# choobMatrix.net
KiCad netlist of a schematic drawn in EAGLE
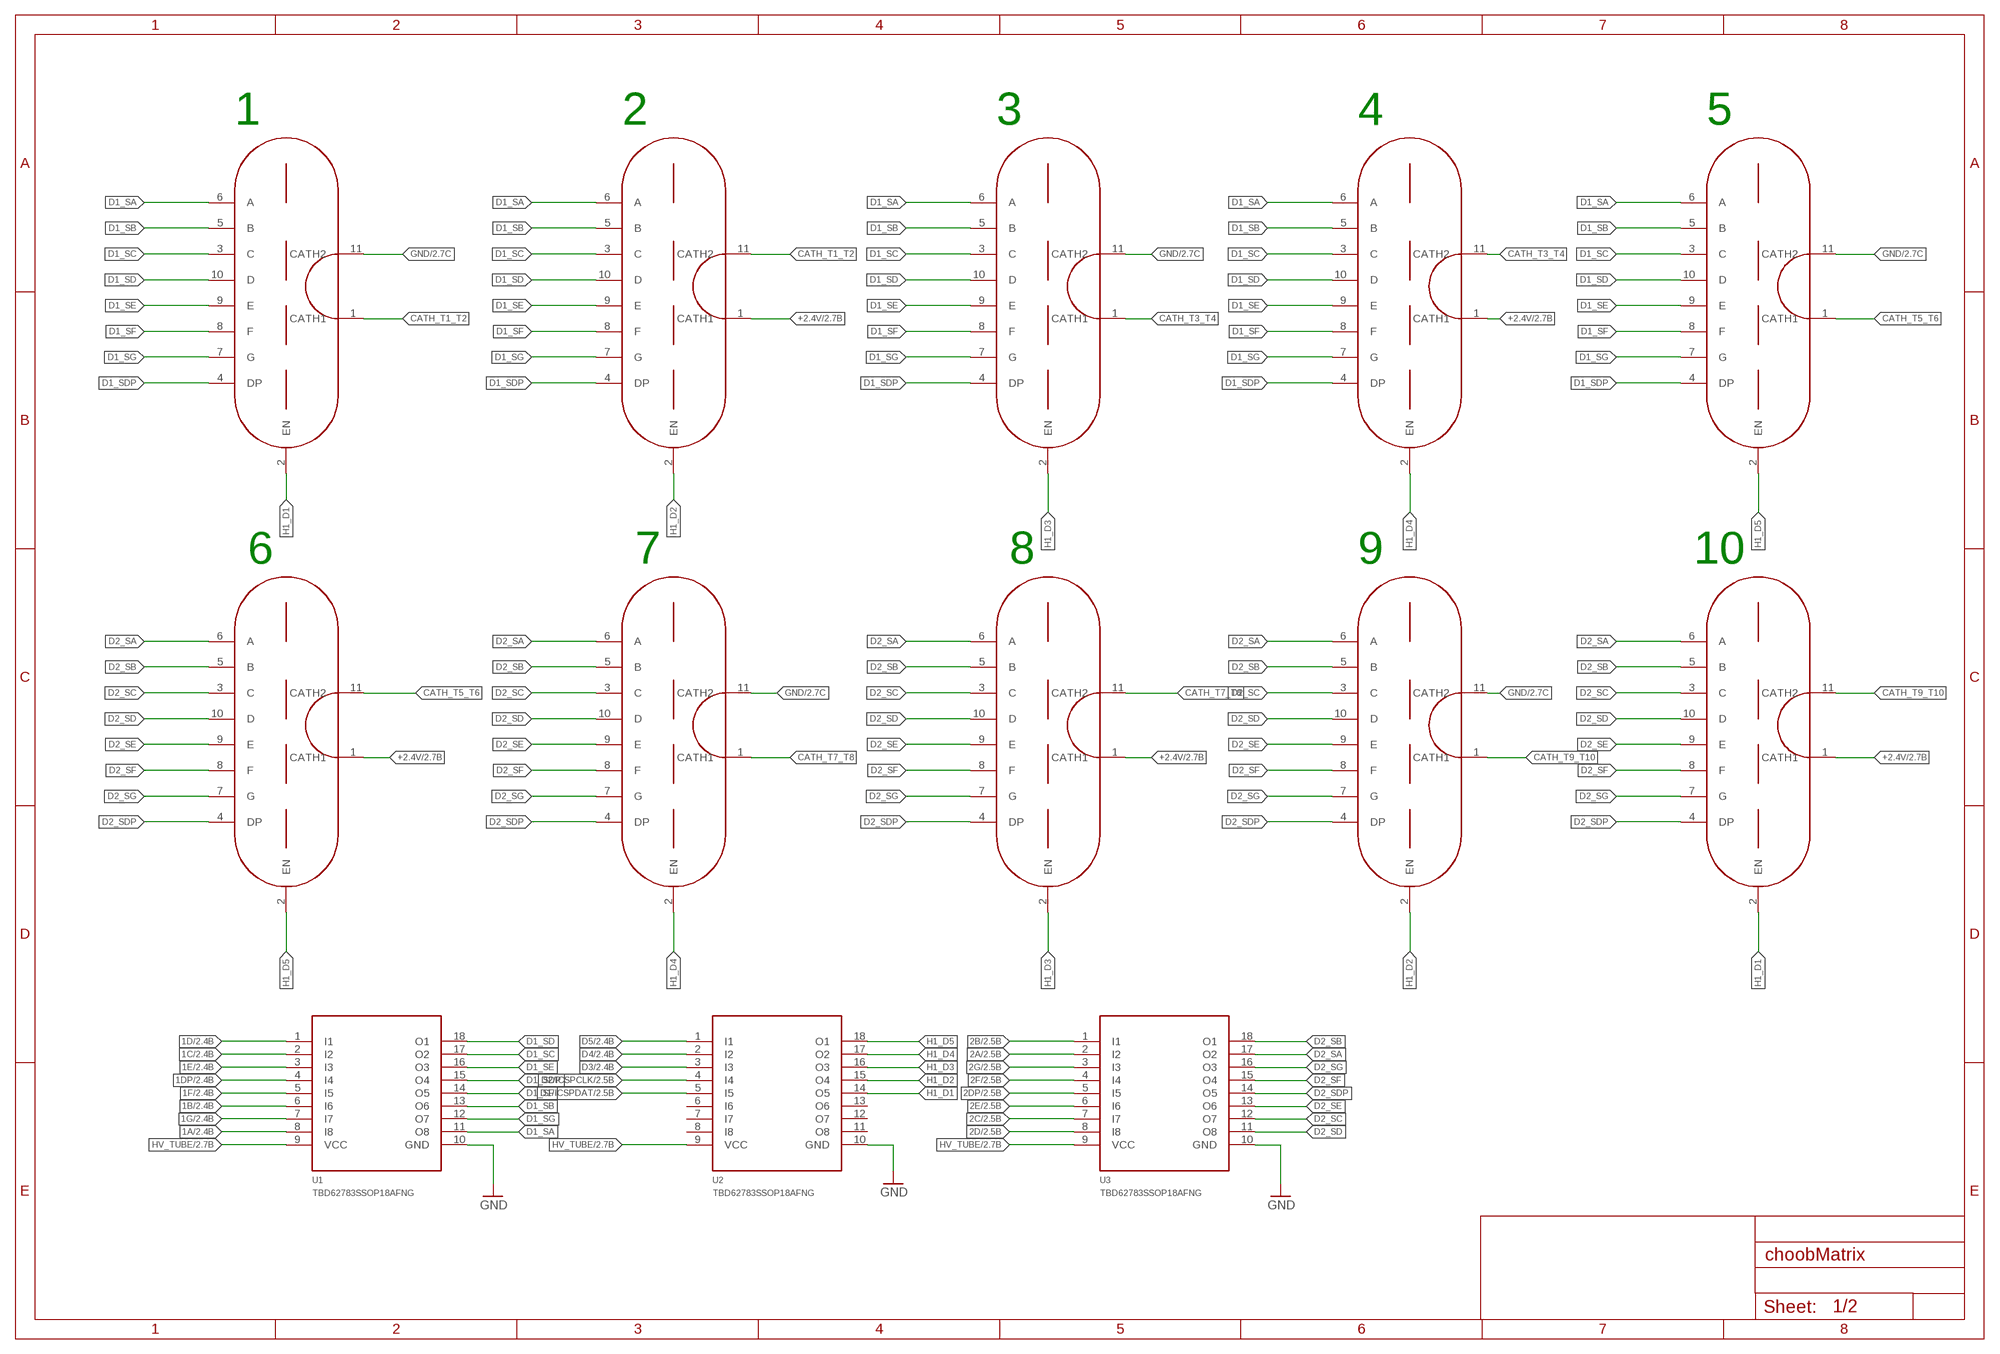
[diagram p0: schematic, sheet 1]
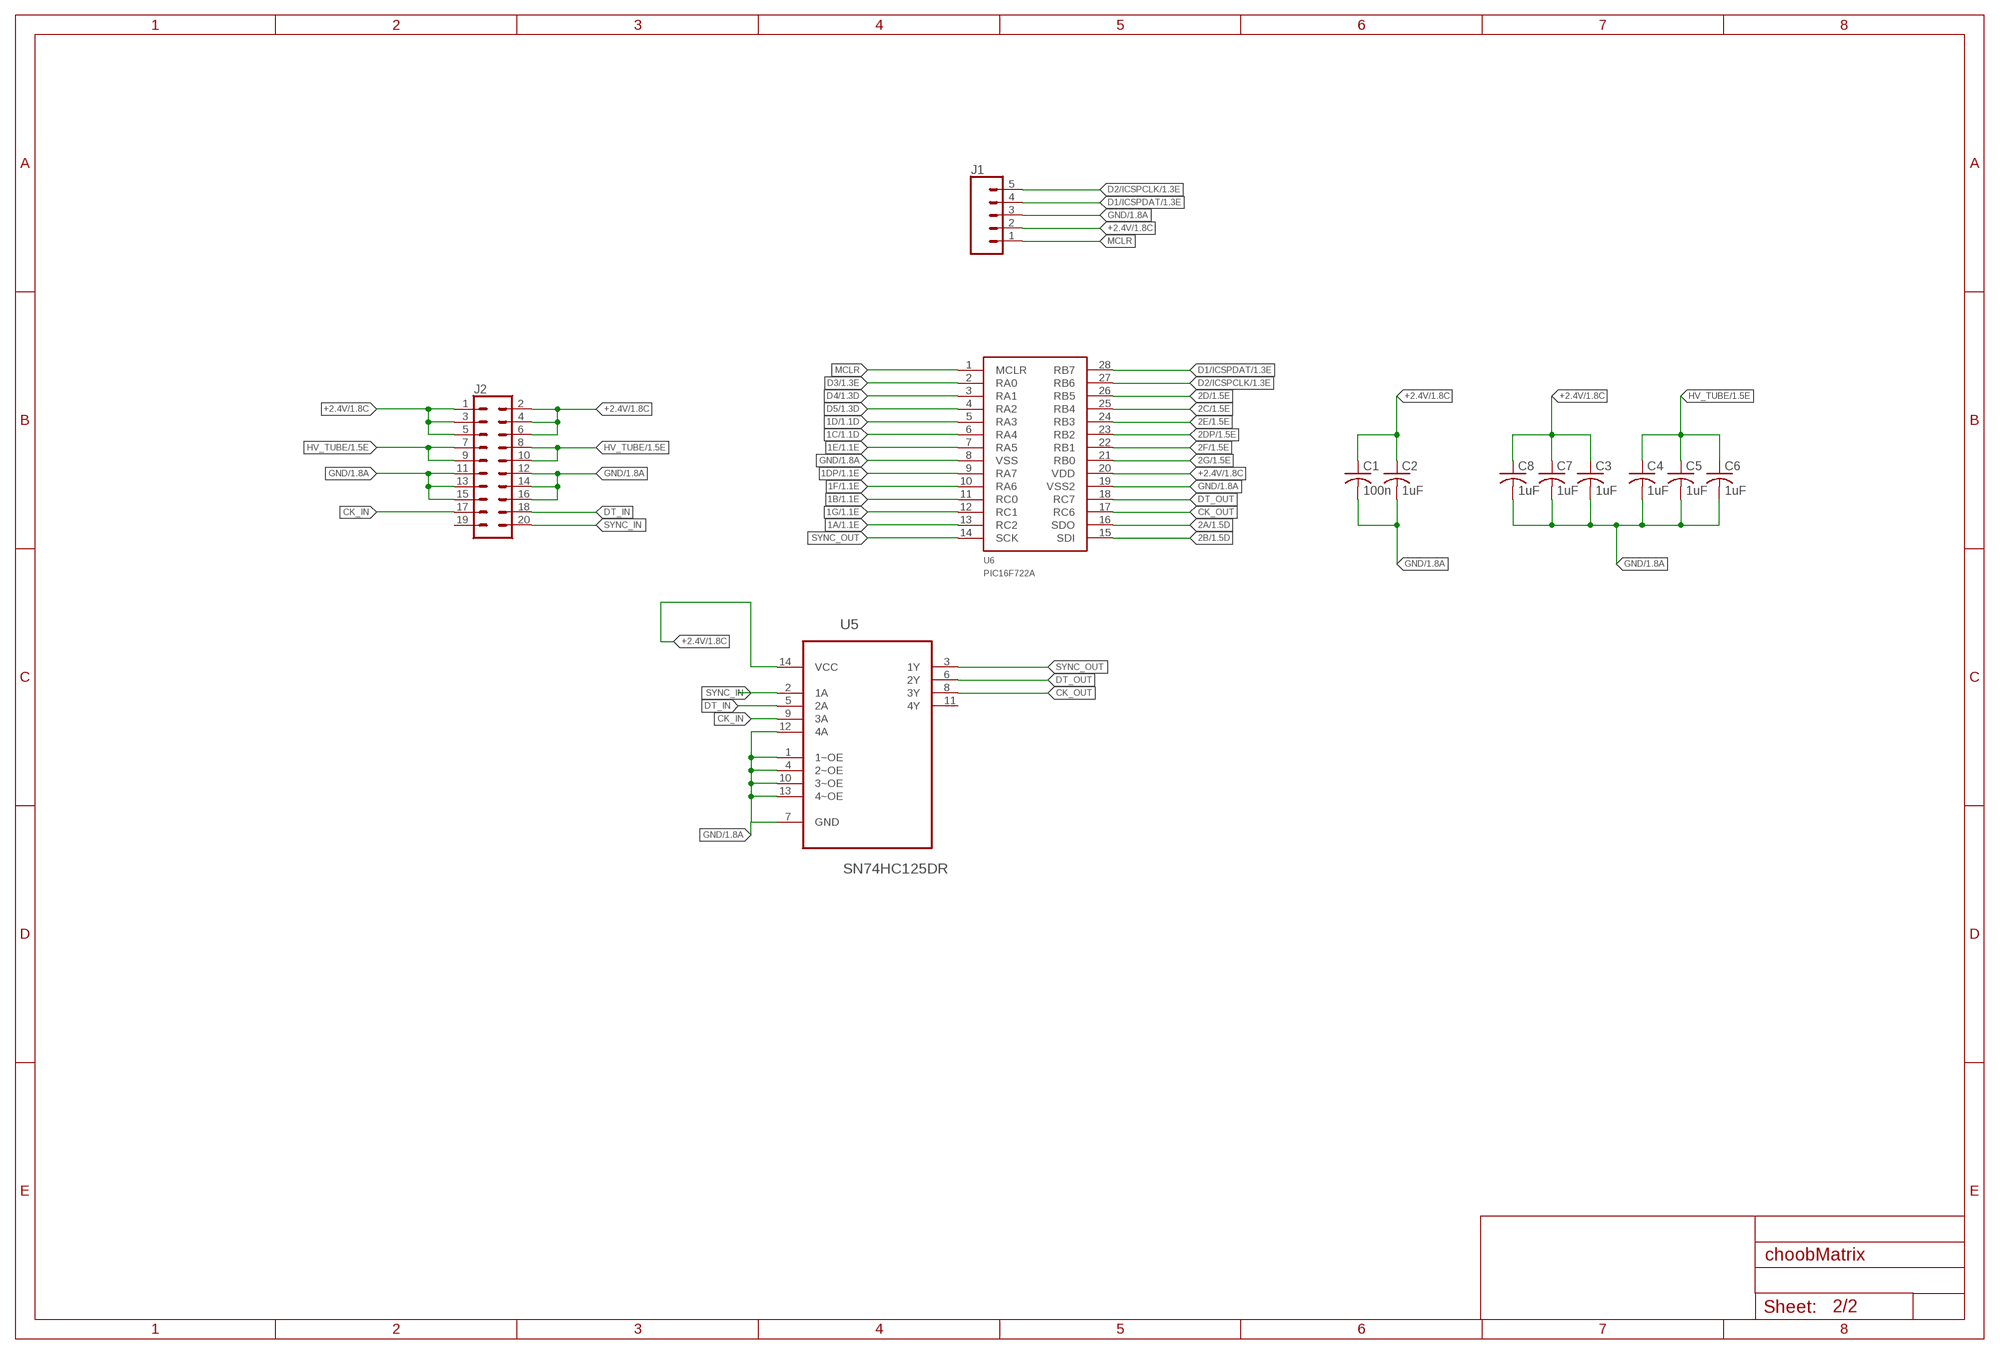
[diagram p1: schematic, sheet 2]

(export (version "E")
  (design (tool "Eeschema 10.0.6"))
  (components
    (comp (ref "C1")
      (value "100n")
      (footprint "eagle-import:C0805K")
      (libsource (lib "eagle-import") (part "C-USC0805K"))
    )
    (comp (ref "C2")
      (value "1uF")
      (footprint "eagle-import:C0805K")
      (libsource (lib "eagle-import") (part "C-USC0805K"))
    )
    (comp (ref "C3")
      (value "1uF")
      (footprint "eagle-import:C0805K")
      (libsource (lib "eagle-import") (part "C-USC0805K"))
    )
    (comp (ref "C4")
      (value "1uF")
      (footprint "eagle-import:C0805K")
      (libsource (lib "eagle-import") (part "C-USC0805K"))
    )
    (comp (ref "C5")
      (value "1uF")
      (footprint "eagle-import:C0805K")
      (libsource (lib "eagle-import") (part "C-USC0805K"))
    )
    (comp (ref "C6")
      (value "1uF")
      (footprint "eagle-import:C0805K")
      (libsource (lib "eagle-import") (part "C-USC0805K"))
    )
    (comp (ref "C7")
      (value "1uF")
      (footprint "eagle-import:C0805K")
      (libsource (lib "eagle-import") (part "C-USC0805K"))
    )
    (comp (ref "C8")
      (value "1uF")
      (footprint "eagle-import:C0805K")
      (libsource (lib "eagle-import") (part "C-USC0805K"))
    )
    (comp (ref "J1")
      (value "CONN_05")
      (footprint "eagle-import:1X05")
      (libsource (lib "eagle-import") (part "CONN_05"))
    )
    (comp (ref "J2")
      (value "CONN_10X2NOSILK")
      (footprint "eagle-import:2X10_NOSILK")
      (libsource (lib "eagle-import") (part "CONN_10X2NOSILK"))
    )
    (comp (ref "U5")
      (value "SN74HC125DR")
      (footprint "eagle-import:SOIC127P600X175-14N")
      (fields (field (name "MF") "Texas Instruments"))
      (libsource (lib "eagle-import") (part "SN74HC125DR"))
    )
    (comp (ref "U6")
      (value "PIC16F722A")
      (footprint "eagle-import:SOP65P780X200-28N")
      (libsource (lib "eagle-import") (part "PIC16F722A"))
    )
    (comp (ref "T1")
      (value "IV11")
      (footprint "eagle-import:IV11")
      (libsource (lib "eagle-import") (part "IV11"))
    )
    (comp (ref "T2")
      (value "IV11")
      (footprint "eagle-import:IV11")
      (libsource (lib "eagle-import") (part "IV11"))
    )
    (comp (ref "T3")
      (value "IV11")
      (footprint "eagle-import:IV11")
      (libsource (lib "eagle-import") (part "IV11"))
    )
    (comp (ref "T4")
      (value "IV11")
      (footprint "eagle-import:IV11")
      (libsource (lib "eagle-import") (part "IV11"))
    )
    (comp (ref "T5")
      (value "IV11")
      (footprint "eagle-import:IV11")
      (libsource (lib "eagle-import") (part "IV11"))
    )
    (comp (ref "T6")
      (value "IV11")
      (footprint "eagle-import:IV11")
      (libsource (lib "eagle-import") (part "IV11"))
    )
    (comp (ref "T7")
      (value "IV11")
      (footprint "eagle-import:IV11")
      (libsource (lib "eagle-import") (part "IV11"))
    )
    (comp (ref "T8")
      (value "IV11")
      (footprint "eagle-import:IV11")
      (libsource (lib "eagle-import") (part "IV11"))
    )
    (comp (ref "T9")
      (value "IV11")
      (footprint "eagle-import:IV11")
      (libsource (lib "eagle-import") (part "IV11"))
    )
    (comp (ref "T10")
      (value "IV11")
      (footprint "eagle-import:IV11")
      (libsource (lib "eagle-import") (part "IV11"))
    )
    (comp (ref "U1")
      (value "TBD62783SSOP18AFNG")
      (footprint "eagle-import:SOP65P640X15-18")
      (libsource (lib "eagle-import") (part "TBD62783SSOP18AFNG"))
    )
    (comp (ref "U2")
      (value "TBD62783SSOP18AFNG")
      (footprint "eagle-import:SOP65P640X15-18")
      (libsource (lib "eagle-import") (part "TBD62783SSOP18AFNG"))
    )
    (comp (ref "U3")
      (value "TBD62783SSOP18AFNG")
      (footprint "eagle-import:SOP65P640X15-18")
      (libsource (lib "eagle-import") (part "TBD62783SSOP18AFNG"))
    )
  )
  (nets
    (net (code "1") (name "+2.4V") (class "Default")
      (node (ref "C1") (pin "1") (pinfunction "1_1") (pintype "passive"))
      (node (ref "C2") (pin "1") (pinfunction "1_1") (pintype "passive"))
      (node (ref "C3") (pin "1") (pinfunction "1_1") (pintype "passive"))
      (node (ref "C7") (pin "1") (pinfunction "1_1") (pintype "passive"))
      (node (ref "C8") (pin "1") (pinfunction "1_1") (pintype "passive"))
      (node (ref "J1") (pin "2") (pinfunction "2_2") (pintype "passive"))
      (node (ref "J2") (pin "1") (pinfunction "1_1") (pintype "passive"))
      (node (ref "J2") (pin "2") (pinfunction "2_2") (pintype "passive"))
      (node (ref "J2") (pin "3") (pinfunction "3_3") (pintype "passive"))
      (node (ref "J2") (pin "4") (pinfunction "4_4") (pintype "passive"))
      (node (ref "J2") (pin "5") (pinfunction "5_5") (pintype "passive"))
      (node (ref "J2") (pin "6") (pinfunction "6_6") (pintype "passive"))
      (node (ref "T10") (pin "1") (pinfunction "CATH1_1") (pintype "bidirectional"))
      (node (ref "T2") (pin "1") (pinfunction "CATH1_1") (pintype "bidirectional"))
      (node (ref "T4") (pin "1") (pinfunction "CATH1_1") (pintype "bidirectional"))
      (node (ref "T6") (pin "1") (pinfunction "CATH1_1") (pintype "bidirectional"))
      (node (ref "T8") (pin "1") (pinfunction "CATH1_1") (pintype "bidirectional"))
      (node (ref "U5") (pin "14") (pinfunction "VCC_14") (pintype "power_in"))
      (node (ref "U6") (pin "20") (pinfunction "VDD_20") (pintype "bidirectional"))
    )
    (net (code "2") (name "1A") (class "Default")
      (node (ref "U1") (pin "8") (pinfunction "I8_8") (pintype "bidirectional"))
      (node (ref "U6") (pin "13") (pinfunction "RC2_13") (pintype "bidirectional"))
    )
    (net (code "3") (name "1B") (class "Default")
      (node (ref "U1") (pin "6") (pinfunction "I6_6") (pintype "bidirectional"))
      (node (ref "U6") (pin "11") (pinfunction "RC0_11") (pintype "bidirectional"))
    )
    (net (code "4") (name "1C") (class "Default")
      (node (ref "U1") (pin "2") (pinfunction "I2_2") (pintype "bidirectional"))
      (node (ref "U6") (pin "6") (pinfunction "RA4_6") (pintype "bidirectional"))
    )
    (net (code "5") (name "1D") (class "Default")
      (node (ref "U1") (pin "1") (pinfunction "I1_1") (pintype "bidirectional"))
      (node (ref "U6") (pin "5") (pinfunction "RA3_5") (pintype "bidirectional"))
    )
    (net (code "6") (name "1DP") (class "Default")
      (node (ref "U1") (pin "4") (pinfunction "I4_4") (pintype "bidirectional"))
      (node (ref "U6") (pin "9") (pinfunction "RA7_9") (pintype "bidirectional"))
    )
    (net (code "7") (name "1E") (class "Default")
      (node (ref "U1") (pin "3") (pinfunction "I3_3") (pintype "bidirectional"))
      (node (ref "U6") (pin "7") (pinfunction "RA5_7") (pintype "bidirectional"))
    )
    (net (code "8") (name "1F") (class "Default")
      (node (ref "U1") (pin "5") (pinfunction "I5_5") (pintype "bidirectional"))
      (node (ref "U6") (pin "10") (pinfunction "RA6_10") (pintype "bidirectional"))
    )
    (net (code "9") (name "1G") (class "Default")
      (node (ref "U1") (pin "7") (pinfunction "I7_7") (pintype "bidirectional"))
      (node (ref "U6") (pin "12") (pinfunction "RC1_12") (pintype "bidirectional"))
    )
    (net (code "10") (name "2A") (class "Default")
      (node (ref "U3") (pin "2") (pinfunction "I2_2") (pintype "bidirectional"))
      (node (ref "U6") (pin "16") (pinfunction "SDO_16") (pintype "bidirectional"))
    )
    (net (code "11") (name "2B") (class "Default")
      (node (ref "U3") (pin "1") (pinfunction "I1_1") (pintype "bidirectional"))
      (node (ref "U6") (pin "15") (pinfunction "SDI_15") (pintype "bidirectional"))
    )
    (net (code "12") (name "2C") (class "Default")
      (node (ref "U3") (pin "7") (pinfunction "I7_7") (pintype "bidirectional"))
      (node (ref "U6") (pin "25") (pinfunction "RB4_25") (pintype "bidirectional"))
    )
    (net (code "13") (name "2D") (class "Default")
      (node (ref "U3") (pin "8") (pinfunction "I8_8") (pintype "bidirectional"))
      (node (ref "U6") (pin "26") (pinfunction "RB5_26") (pintype "bidirectional"))
    )
    (net (code "14") (name "2DP") (class "Default")
      (node (ref "U3") (pin "5") (pinfunction "I5_5") (pintype "bidirectional"))
      (node (ref "U6") (pin "23") (pinfunction "RB2_23") (pintype "bidirectional"))
    )
    (net (code "15") (name "2E") (class "Default")
      (node (ref "U3") (pin "6") (pinfunction "I6_6") (pintype "bidirectional"))
      (node (ref "U6") (pin "24") (pinfunction "RB3_24") (pintype "bidirectional"))
    )
    (net (code "16") (name "2F") (class "Default")
      (node (ref "U3") (pin "4") (pinfunction "I4_4") (pintype "bidirectional"))
      (node (ref "U6") (pin "22") (pinfunction "RB1_22") (pintype "bidirectional"))
    )
    (net (code "17") (name "2G") (class "Default")
      (node (ref "U3") (pin "3") (pinfunction "I3_3") (pintype "bidirectional"))
      (node (ref "U6") (pin "21") (pinfunction "RB0_21") (pintype "bidirectional"))
    )
    (net (code "18") (name "CATH_T1_T2") (class "Default")
      (node (ref "T1") (pin "1") (pinfunction "CATH1_1") (pintype "bidirectional"))
      (node (ref "T2") (pin "11") (pinfunction "CATH2_11") (pintype "bidirectional"))
    )
    (net (code "19") (name "CATH_T3_T4") (class "Default")
      (node (ref "T3") (pin "1") (pinfunction "CATH1_1") (pintype "bidirectional"))
      (node (ref "T4") (pin "11") (pinfunction "CATH2_11") (pintype "bidirectional"))
    )
    (net (code "20") (name "CATH_T5_T6") (class "Default")
      (node (ref "T5") (pin "1") (pinfunction "CATH1_1") (pintype "bidirectional"))
      (node (ref "T6") (pin "11") (pinfunction "CATH2_11") (pintype "bidirectional"))
    )
    (net (code "21") (name "CATH_T7_T8") (class "Default")
      (node (ref "T7") (pin "1") (pinfunction "CATH1_1") (pintype "bidirectional"))
      (node (ref "T8") (pin "11") (pinfunction "CATH2_11") (pintype "bidirectional"))
    )
    (net (code "22") (name "CATH_T9_T10") (class "Default")
      (node (ref "T10") (pin "11") (pinfunction "CATH2_11") (pintype "bidirectional"))
      (node (ref "T9") (pin "1") (pinfunction "CATH1_1") (pintype "bidirectional"))
    )
    (net (code "23") (name "CK_IN") (class "Default")
      (node (ref "J2") (pin "17") (pinfunction "17_17") (pintype "passive"))
      (node (ref "U5") (pin "9") (pinfunction "3A_9") (pintype "input"))
    )
    (net (code "24") (name "CK_OUT") (class "Default")
      (node (ref "U5") (pin "8") (pinfunction "3Y_8") (pintype "output"))
      (node (ref "U6") (pin "17") (pinfunction "RC6_17") (pintype "bidirectional"))
    )
    (net (code "25") (name "D1_SA") (class "Default")
      (node (ref "T1") (pin "6") (pinfunction "A_6") (pintype "bidirectional"))
      (node (ref "T2") (pin "6") (pinfunction "A_6") (pintype "bidirectional"))
      (node (ref "T3") (pin "6") (pinfunction "A_6") (pintype "bidirectional"))
      (node (ref "T4") (pin "6") (pinfunction "A_6") (pintype "bidirectional"))
      (node (ref "T5") (pin "6") (pinfunction "A_6") (pintype "bidirectional"))
      (node (ref "U1") (pin "11") (pinfunction "O8_11") (pintype "bidirectional"))
    )
    (net (code "26") (name "D1_SB") (class "Default")
      (node (ref "T1") (pin "5") (pinfunction "B_5") (pintype "bidirectional"))
      (node (ref "T2") (pin "5") (pinfunction "B_5") (pintype "bidirectional"))
      (node (ref "T3") (pin "5") (pinfunction "B_5") (pintype "bidirectional"))
      (node (ref "T4") (pin "5") (pinfunction "B_5") (pintype "bidirectional"))
      (node (ref "T5") (pin "5") (pinfunction "B_5") (pintype "bidirectional"))
      (node (ref "U1") (pin "13") (pinfunction "O6_13") (pintype "bidirectional"))
    )
    (net (code "27") (name "D1_SC") (class "Default")
      (node (ref "T1") (pin "3") (pinfunction "C_3") (pintype "bidirectional"))
      (node (ref "T2") (pin "3") (pinfunction "C_3") (pintype "bidirectional"))
      (node (ref "T3") (pin "3") (pinfunction "C_3") (pintype "bidirectional"))
      (node (ref "T4") (pin "3") (pinfunction "C_3") (pintype "bidirectional"))
      (node (ref "T5") (pin "3") (pinfunction "C_3") (pintype "bidirectional"))
      (node (ref "U1") (pin "17") (pinfunction "O2_17") (pintype "bidirectional"))
    )
    (net (code "28") (name "D1_SD") (class "Default")
      (node (ref "T1") (pin "10") (pinfunction "D_10") (pintype "bidirectional"))
      (node (ref "T2") (pin "10") (pinfunction "D_10") (pintype "bidirectional"))
      (node (ref "T3") (pin "10") (pinfunction "D_10") (pintype "bidirectional"))
      (node (ref "T4") (pin "10") (pinfunction "D_10") (pintype "bidirectional"))
      (node (ref "T5") (pin "10") (pinfunction "D_10") (pintype "bidirectional"))
      (node (ref "U1") (pin "18") (pinfunction "O1_18") (pintype "bidirectional"))
    )
    (net (code "29") (name "D1_SDP") (class "Default")
      (node (ref "T1") (pin "4") (pinfunction "DP_4") (pintype "bidirectional"))
      (node (ref "T2") (pin "4") (pinfunction "DP_4") (pintype "bidirectional"))
      (node (ref "T3") (pin "4") (pinfunction "DP_4") (pintype "bidirectional"))
      (node (ref "T4") (pin "4") (pinfunction "DP_4") (pintype "bidirectional"))
      (node (ref "T5") (pin "4") (pinfunction "DP_4") (pintype "bidirectional"))
      (node (ref "U1") (pin "15") (pinfunction "O4_15") (pintype "bidirectional"))
    )
    (net (code "30") (name "D1_SE") (class "Default")
      (node (ref "T1") (pin "9") (pinfunction "E_9") (pintype "bidirectional"))
      (node (ref "T2") (pin "9") (pinfunction "E_9") (pintype "bidirectional"))
      (node (ref "T3") (pin "9") (pinfunction "E_9") (pintype "bidirectional"))
      (node (ref "T4") (pin "9") (pinfunction "E_9") (pintype "bidirectional"))
      (node (ref "T5") (pin "9") (pinfunction "E_9") (pintype "bidirectional"))
      (node (ref "U1") (pin "16") (pinfunction "O3_16") (pintype "bidirectional"))
    )
    (net (code "31") (name "D1_SF") (class "Default")
      (node (ref "T1") (pin "8") (pinfunction "F_8") (pintype "bidirectional"))
      (node (ref "T2") (pin "8") (pinfunction "F_8") (pintype "bidirectional"))
      (node (ref "T3") (pin "8") (pinfunction "F_8") (pintype "bidirectional"))
      (node (ref "T4") (pin "8") (pinfunction "F_8") (pintype "bidirectional"))
      (node (ref "T5") (pin "8") (pinfunction "F_8") (pintype "bidirectional"))
      (node (ref "U1") (pin "14") (pinfunction "O5_14") (pintype "bidirectional"))
    )
    (net (code "32") (name "D1_SG") (class "Default")
      (node (ref "T1") (pin "7") (pinfunction "G_7") (pintype "bidirectional"))
      (node (ref "T2") (pin "7") (pinfunction "G_7") (pintype "bidirectional"))
      (node (ref "T3") (pin "7") (pinfunction "G_7") (pintype "bidirectional"))
      (node (ref "T4") (pin "7") (pinfunction "G_7") (pintype "bidirectional"))
      (node (ref "T5") (pin "7") (pinfunction "G_7") (pintype "bidirectional"))
      (node (ref "U1") (pin "12") (pinfunction "O7_12") (pintype "bidirectional"))
    )
    (net (code "33") (name "D1{slash}ICSPDAT") (class "Default")
      (node (ref "J1") (pin "4") (pinfunction "4_4") (pintype "passive"))
      (node (ref "U2") (pin "5") (pinfunction "I5_5") (pintype "bidirectional"))
      (node (ref "U6") (pin "28") (pinfunction "RB7_28") (pintype "bidirectional"))
    )
    (net (code "34") (name "D2_SA") (class "Default")
      (node (ref "T10") (pin "6") (pinfunction "A_6") (pintype "bidirectional"))
      (node (ref "T6") (pin "6") (pinfunction "A_6") (pintype "bidirectional"))
      (node (ref "T7") (pin "6") (pinfunction "A_6") (pintype "bidirectional"))
      (node (ref "T8") (pin "6") (pinfunction "A_6") (pintype "bidirectional"))
      (node (ref "T9") (pin "6") (pinfunction "A_6") (pintype "bidirectional"))
      (node (ref "U3") (pin "17") (pinfunction "O2_17") (pintype "bidirectional"))
    )
    (net (code "35") (name "D2_SB") (class "Default")
      (node (ref "T10") (pin "5") (pinfunction "B_5") (pintype "bidirectional"))
      (node (ref "T6") (pin "5") (pinfunction "B_5") (pintype "bidirectional"))
      (node (ref "T7") (pin "5") (pinfunction "B_5") (pintype "bidirectional"))
      (node (ref "T8") (pin "5") (pinfunction "B_5") (pintype "bidirectional"))
      (node (ref "T9") (pin "5") (pinfunction "B_5") (pintype "bidirectional"))
      (node (ref "U3") (pin "18") (pinfunction "O1_18") (pintype "bidirectional"))
    )
    (net (code "36") (name "D2_SC") (class "Default")
      (node (ref "T10") (pin "3") (pinfunction "C_3") (pintype "bidirectional"))
      (node (ref "T6") (pin "3") (pinfunction "C_3") (pintype "bidirectional"))
      (node (ref "T7") (pin "3") (pinfunction "C_3") (pintype "bidirectional"))
      (node (ref "T8") (pin "3") (pinfunction "C_3") (pintype "bidirectional"))
      (node (ref "T9") (pin "3") (pinfunction "C_3") (pintype "bidirectional"))
      (node (ref "U3") (pin "12") (pinfunction "O7_12") (pintype "bidirectional"))
    )
    (net (code "37") (name "D2_SD") (class "Default")
      (node (ref "T10") (pin "10") (pinfunction "D_10") (pintype "bidirectional"))
      (node (ref "T6") (pin "10") (pinfunction "D_10") (pintype "bidirectional"))
      (node (ref "T7") (pin "10") (pinfunction "D_10") (pintype "bidirectional"))
      (node (ref "T8") (pin "10") (pinfunction "D_10") (pintype "bidirectional"))
      (node (ref "T9") (pin "10") (pinfunction "D_10") (pintype "bidirectional"))
      (node (ref "U3") (pin "11") (pinfunction "O8_11") (pintype "bidirectional"))
    )
    (net (code "38") (name "D2_SDP") (class "Default")
      (node (ref "T10") (pin "4") (pinfunction "DP_4") (pintype "bidirectional"))
      (node (ref "T6") (pin "4") (pinfunction "DP_4") (pintype "bidirectional"))
      (node (ref "T7") (pin "4") (pinfunction "DP_4") (pintype "bidirectional"))
      (node (ref "T8") (pin "4") (pinfunction "DP_4") (pintype "bidirectional"))
      (node (ref "T9") (pin "4") (pinfunction "DP_4") (pintype "bidirectional"))
      (node (ref "U3") (pin "14") (pinfunction "O5_14") (pintype "bidirectional"))
    )
    (net (code "39") (name "D2_SE") (class "Default")
      (node (ref "T10") (pin "9") (pinfunction "E_9") (pintype "bidirectional"))
      (node (ref "T6") (pin "9") (pinfunction "E_9") (pintype "bidirectional"))
      (node (ref "T7") (pin "9") (pinfunction "E_9") (pintype "bidirectional"))
      (node (ref "T8") (pin "9") (pinfunction "E_9") (pintype "bidirectional"))
      (node (ref "T9") (pin "9") (pinfunction "E_9") (pintype "bidirectional"))
      (node (ref "U3") (pin "13") (pinfunction "O6_13") (pintype "bidirectional"))
    )
    (net (code "40") (name "D2_SF") (class "Default")
      (node (ref "T10") (pin "8") (pinfunction "F_8") (pintype "bidirectional"))
      (node (ref "T6") (pin "8") (pinfunction "F_8") (pintype "bidirectional"))
      (node (ref "T7") (pin "8") (pinfunction "F_8") (pintype "bidirectional"))
      (node (ref "T8") (pin "8") (pinfunction "F_8") (pintype "bidirectional"))
      (node (ref "T9") (pin "8") (pinfunction "F_8") (pintype "bidirectional"))
      (node (ref "U3") (pin "15") (pinfunction "O4_15") (pintype "bidirectional"))
    )
    (net (code "41") (name "D2_SG") (class "Default")
      (node (ref "T10") (pin "7") (pinfunction "G_7") (pintype "bidirectional"))
      (node (ref "T6") (pin "7") (pinfunction "G_7") (pintype "bidirectional"))
      (node (ref "T7") (pin "7") (pinfunction "G_7") (pintype "bidirectional"))
      (node (ref "T8") (pin "7") (pinfunction "G_7") (pintype "bidirectional"))
      (node (ref "T9") (pin "7") (pinfunction "G_7") (pintype "bidirectional"))
      (node (ref "U3") (pin "16") (pinfunction "O3_16") (pintype "bidirectional"))
    )
    (net (code "42") (name "D2{slash}ICSPCLK") (class "Default")
      (node (ref "J1") (pin "5") (pinfunction "5_5") (pintype "passive"))
      (node (ref "U2") (pin "4") (pinfunction "I4_4") (pintype "bidirectional"))
      (node (ref "U6") (pin "27") (pinfunction "RB6_27") (pintype "bidirectional"))
    )
    (net (code "43") (name "D3") (class "Default")
      (node (ref "U2") (pin "3") (pinfunction "I3_3") (pintype "bidirectional"))
      (node (ref "U6") (pin "2") (pinfunction "RA0_2") (pintype "bidirectional"))
    )
    (net (code "44") (name "D4") (class "Default")
      (node (ref "U2") (pin "2") (pinfunction "I2_2") (pintype "bidirectional"))
      (node (ref "U6") (pin "3") (pinfunction "RA1_3") (pintype "bidirectional"))
    )
    (net (code "45") (name "D5") (class "Default")
      (node (ref "U2") (pin "1") (pinfunction "I1_1") (pintype "bidirectional"))
      (node (ref "U6") (pin "4") (pinfunction "RA2_4") (pintype "bidirectional"))
    )
    (net (code "46") (name "DT_IN") (class "Default")
      (node (ref "J2") (pin "18") (pinfunction "18_18") (pintype "passive"))
      (node (ref "U5") (pin "5") (pinfunction "2A_5") (pintype "input"))
    )
    (net (code "47") (name "DT_OUT") (class "Default")
      (node (ref "U5") (pin "6") (pinfunction "2Y_6") (pintype "output"))
      (node (ref "U6") (pin "18") (pinfunction "RC7_18") (pintype "bidirectional"))
    )
    (net (code "48") (name "GND") (class "Default")
      (node (ref "C1") (pin "2") (pinfunction "2_2") (pintype "passive"))
      (node (ref "C2") (pin "2") (pinfunction "2_2") (pintype "passive"))
      (node (ref "C3") (pin "2") (pinfunction "2_2") (pintype "passive"))
      (node (ref "C4") (pin "2") (pinfunction "2_2") (pintype "passive"))
      (node (ref "C5") (pin "2") (pinfunction "2_2") (pintype "passive"))
      (node (ref "C6") (pin "2") (pinfunction "2_2") (pintype "passive"))
      (node (ref "C7") (pin "2") (pinfunction "2_2") (pintype "passive"))
      (node (ref "C8") (pin "2") (pinfunction "2_2") (pintype "passive"))
      (node (ref "J1") (pin "3") (pinfunction "3_3") (pintype "passive"))
      (node (ref "J2") (pin "11") (pinfunction "11_11") (pintype "passive"))
      (node (ref "J2") (pin "12") (pinfunction "12_12") (pintype "passive"))
      (node (ref "J2") (pin "13") (pinfunction "13_13") (pintype "passive"))
      (node (ref "J2") (pin "14") (pinfunction "14_14") (pintype "passive"))
      (node (ref "J2") (pin "15") (pinfunction "15_15") (pintype "passive"))
      (node (ref "J2") (pin "16") (pinfunction "16_16") (pintype "passive"))
      (node (ref "T1") (pin "11") (pinfunction "CATH2_11") (pintype "bidirectional"))
      (node (ref "T3") (pin "11") (pinfunction "CATH2_11") (pintype "bidirectional"))
      (node (ref "T5") (pin "11") (pinfunction "CATH2_11") (pintype "bidirectional"))
      (node (ref "T7") (pin "11") (pinfunction "CATH2_11") (pintype "bidirectional"))
      (node (ref "T9") (pin "11") (pinfunction "CATH2_11") (pintype "bidirectional"))
      (node (ref "U1") (pin "10") (pinfunction "GND_10") (pintype "bidirectional"))
      (node (ref "U2") (pin "10") (pinfunction "GND_10") (pintype "bidirectional"))
      (node (ref "U3") (pin "10") (pinfunction "GND_10") (pintype "bidirectional"))
      (node (ref "U5") (pin "1") (pinfunction "1~{OE}_1") (pintype "input"))
      (node (ref "U5") (pin "10") (pinfunction "3~{OE}_10") (pintype "input"))
      (node (ref "U5") (pin "12") (pinfunction "4A_12") (pintype "input"))
      (node (ref "U5") (pin "13") (pinfunction "4~{OE}_13") (pintype "input"))
      (node (ref "U5") (pin "4") (pinfunction "2~{OE}_4") (pintype "input"))
      (node (ref "U5") (pin "7") (pinfunction "GND_7") (pintype "passive"))
      (node (ref "U6") (pin "19") (pinfunction "VSS2_19") (pintype "bidirectional"))
      (node (ref "U6") (pin "8") (pinfunction "VSS_8") (pintype "bidirectional"))
    )
    (net (code "49") (name "H1_D1") (class "Default")
      (node (ref "T1") (pin "2") (pinfunction "EN_2") (pintype "bidirectional"))
      (node (ref "T10") (pin "2") (pinfunction "EN_2") (pintype "bidirectional"))
      (node (ref "U2") (pin "14") (pinfunction "O5_14") (pintype "bidirectional"))
    )
    (net (code "50") (name "H1_D2") (class "Default")
      (node (ref "T2") (pin "2") (pinfunction "EN_2") (pintype "bidirectional"))
      (node (ref "T9") (pin "2") (pinfunction "EN_2") (pintype "bidirectional"))
      (node (ref "U2") (pin "15") (pinfunction "O4_15") (pintype "bidirectional"))
    )
    (net (code "51") (name "H1_D3") (class "Default")
      (node (ref "T3") (pin "2") (pinfunction "EN_2") (pintype "bidirectional"))
      (node (ref "T8") (pin "2") (pinfunction "EN_2") (pintype "bidirectional"))
      (node (ref "U2") (pin "16") (pinfunction "O3_16") (pintype "bidirectional"))
    )
    (net (code "52") (name "H1_D4") (class "Default")
      (node (ref "T4") (pin "2") (pinfunction "EN_2") (pintype "bidirectional"))
      (node (ref "T7") (pin "2") (pinfunction "EN_2") (pintype "bidirectional"))
      (node (ref "U2") (pin "17") (pinfunction "O2_17") (pintype "bidirectional"))
    )
    (net (code "53") (name "H1_D5") (class "Default")
      (node (ref "T5") (pin "2") (pinfunction "EN_2") (pintype "bidirectional"))
      (node (ref "T6") (pin "2") (pinfunction "EN_2") (pintype "bidirectional"))
      (node (ref "U2") (pin "18") (pinfunction "O1_18") (pintype "bidirectional"))
    )
    (net (code "54") (name "HV_TUBE") (class "Default")
      (node (ref "C4") (pin "1") (pinfunction "1_1") (pintype "passive"))
      (node (ref "C5") (pin "1") (pinfunction "1_1") (pintype "passive"))
      (node (ref "C6") (pin "1") (pinfunction "1_1") (pintype "passive"))
      (node (ref "J2") (pin "10") (pinfunction "10_10") (pintype "passive"))
      (node (ref "J2") (pin "7") (pinfunction "7_7") (pintype "passive"))
      (node (ref "J2") (pin "8") (pinfunction "8_8") (pintype "passive"))
      (node (ref "J2") (pin "9") (pinfunction "9_9") (pintype "passive"))
      (node (ref "U1") (pin "9") (pinfunction "VCC_9") (pintype "bidirectional"))
      (node (ref "U2") (pin "9") (pinfunction "VCC_9") (pintype "bidirectional"))
      (node (ref "U3") (pin "9") (pinfunction "VCC_9") (pintype "bidirectional"))
    )
    (net (code "55") (name "MCLR") (class "Default")
      (node (ref "J1") (pin "1") (pinfunction "1_1") (pintype "passive"))
      (node (ref "U6") (pin "1") (pinfunction "MCLR_1") (pintype "bidirectional"))
    )
    (net (code "56") (name "SYNC_IN") (class "Default")
      (node (ref "J2") (pin "20") (pinfunction "20_20") (pintype "passive"))
      (node (ref "U5") (pin "2") (pinfunction "1A_2") (pintype "input"))
    )
    (net (code "57") (name "SYNC_OUT") (class "Default")
      (node (ref "U5") (pin "3") (pinfunction "1Y_3") (pintype "output"))
      (node (ref "U6") (pin "14") (pinfunction "SCK_14") (pintype "bidirectional"))
    )
    (net (code "58") (name "unconnected-(J2-Pad19)") (class "Default")
      (node (ref "J2") (pin "19") (pinfunction "19_19") (pintype "passive"))
    )
    (net (code "59") (name "unconnected-(U2-I6-Pad6)") (class "Default")
      (node (ref "U2") (pin "6") (pinfunction "I6_6") (pintype "bidirectional"))
    )
    (net (code "60") (name "unconnected-(U2-I7-Pad7)") (class "Default")
      (node (ref "U2") (pin "7") (pinfunction "I7_7") (pintype "bidirectional"))
    )
    (net (code "61") (name "unconnected-(U2-I8-Pad8)") (class "Default")
      (node (ref "U2") (pin "8") (pinfunction "I8_8") (pintype "bidirectional"))
    )
    (net (code "62") (name "unconnected-(U2-O6-Pad13)") (class "Default")
      (node (ref "U2") (pin "13") (pinfunction "O6_13") (pintype "bidirectional"))
    )
    (net (code "63") (name "unconnected-(U2-O7-Pad12)") (class "Default")
      (node (ref "U2") (pin "12") (pinfunction "O7_12") (pintype "bidirectional"))
    )
    (net (code "64") (name "unconnected-(U2-O8-Pad11)") (class "Default")
      (node (ref "U2") (pin "11") (pinfunction "O8_11") (pintype "bidirectional"))
    )
    (net (code "65") (name "unconnected-(U5-4Y-Pad11)") (class "Default")
      (node (ref "U5") (pin "11") (pinfunction "4Y_11") (pintype "output"))
    )
  )
)
